# 06_POWER_4.net
KiCad netlist of a schematic drawn in Altium Designer
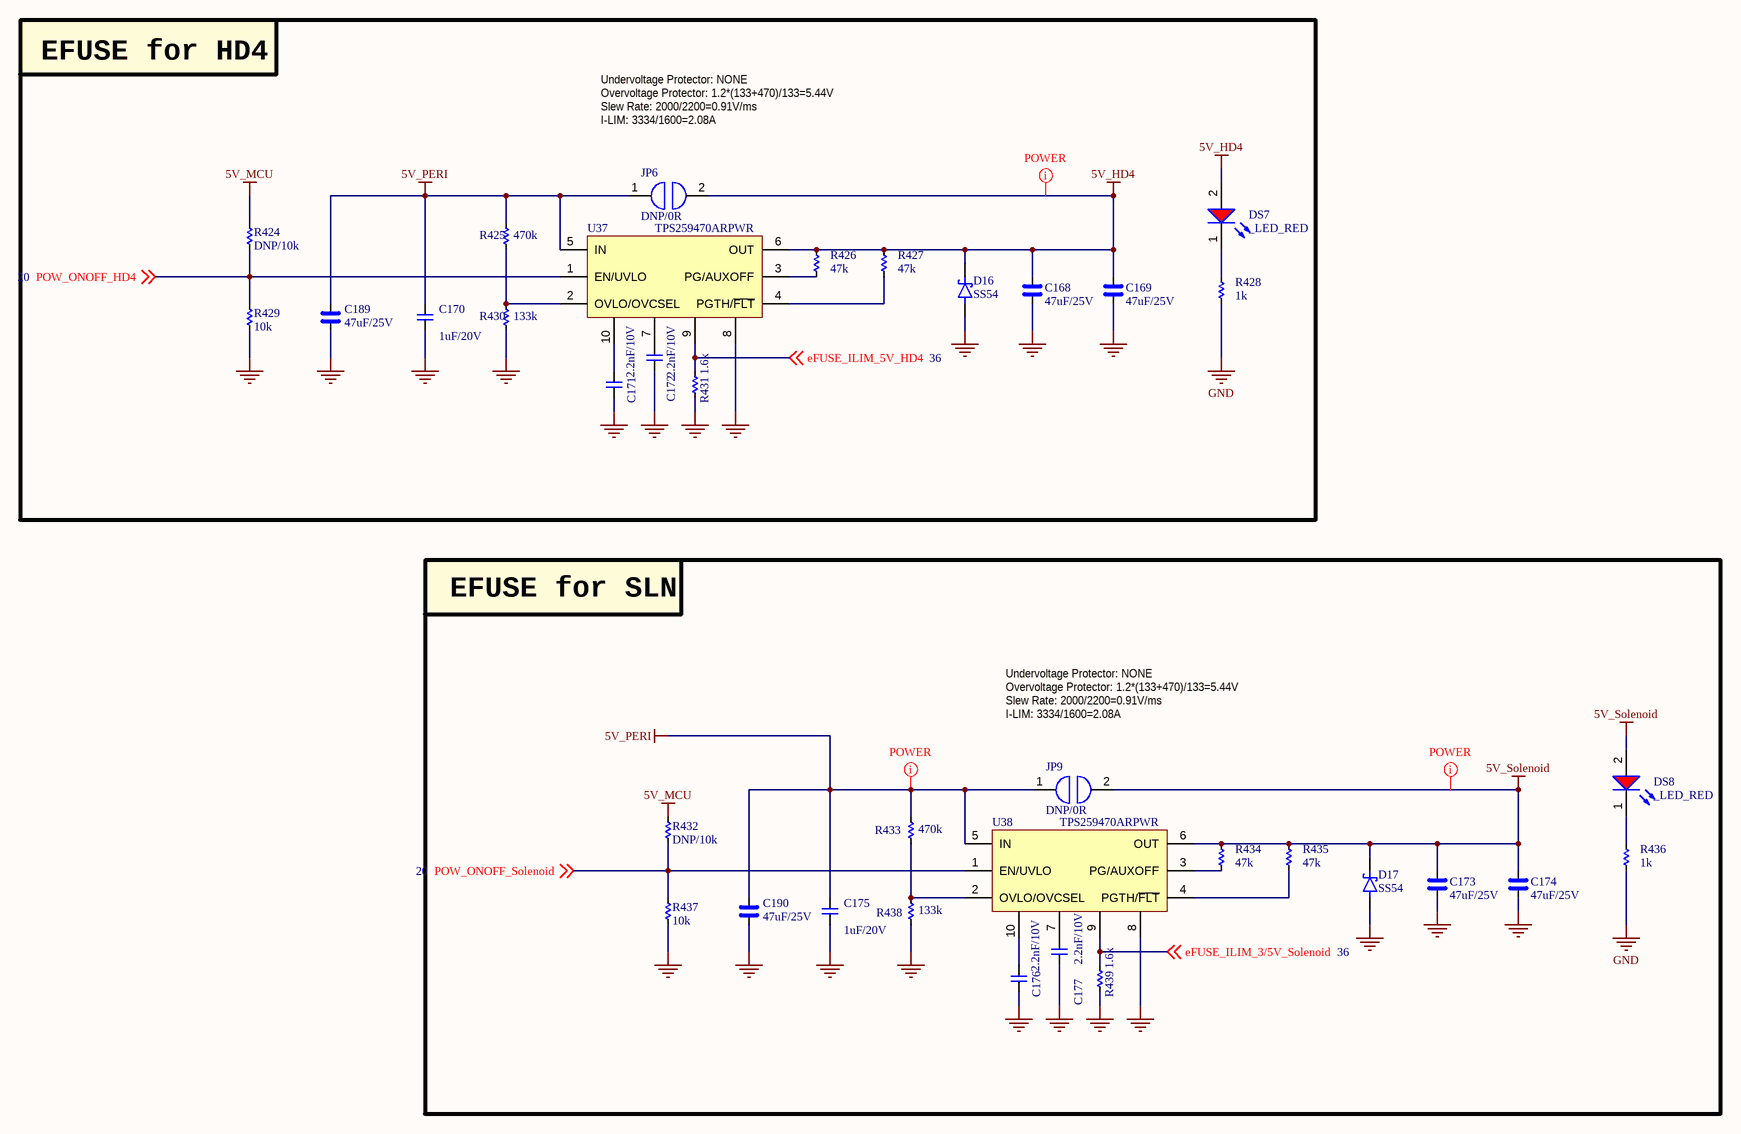
[diagram p0: 06_POWER_4.SchDoc]

(export (version "E")
  (design (tool "Eeschema 10.0.6"))
  (components
    (comp (ref "C168")
      (value "47uF/25V")
      (footprint "CAP_C_3225X80")
      (description "CAP High Value")
      (libsource (lib "LABLIB") (part "_CAP_C_High_2"))
    )
    (comp (ref "C169")
      (value "47uF/25V")
      (footprint "CAP_C_3225X80")
      (description "CAP High Value")
      (libsource (lib "LABLIB") (part "_CAP_C_High_2"))
    )
    (comp (ref "C170")
      (value "1uF/20V")
      (footprint "CAP_C_1005X60")
      (description "CAP")
      (libsource (lib "LABLIB") (part "_CAP_C_2"))
    )
    (comp (ref "C171")
      (value "2.2nF/10V")
      (footprint "CAP_C_1005X60")
      (description "CAP")
      (libsource (lib "LABLIB") (part "_CAP_C_2"))
    )
    (comp (ref "C172")
      (value "2.2nF/10V")
      (footprint "CAP_C_1005X60")
      (description "CAP")
      (libsource (lib "LABLIB") (part "_CAP_C_2"))
    )
    (comp (ref "C173")
      (value "47uF/25V")
      (footprint "CAP_C_3225X80")
      (description "CAP High Value")
      (libsource (lib "LABLIB") (part "_CAP_C_High_2"))
    )
    (comp (ref "C174")
      (value "47uF/25V")
      (footprint "CAP_C_3225X80")
      (description "CAP High Value")
      (libsource (lib "LABLIB") (part "_CAP_C_High_2"))
    )
    (comp (ref "C175")
      (value "1uF/20V")
      (footprint "CAP_C_1005X60")
      (description "CAP")
      (libsource (lib "LABLIB") (part "_CAP_C_2"))
    )
    (comp (ref "C176")
      (value "2.2nF/10V")
      (footprint "CAP_C_1005X60")
      (description "CAP")
      (libsource (lib "LABLIB") (part "_CAP_C_2"))
    )
    (comp (ref "C177")
      (value "2.2nF/10V")
      (footprint "CAP_C_1005X60")
      (description "CAP")
      (libsource (lib "LABLIB") (part "_CAP_C_2"))
    )
    (comp (ref "C189")
      (value "47uF/25V")
      (footprint "CAP_C_3225X80")
      (description "CAP High Value")
      (libsource (lib "LABLIB") (part "_CAP_C_High_2"))
    )
    (comp (ref "C190")
      (value "47uF/25V")
      (footprint "CAP_C_3225X80")
      (description "CAP High Value")
      (libsource (lib "LABLIB") (part "_CAP_C_High_2"))
    )
    (comp (ref "D16")
      (value "SS54")
      (footprint "DO-214AC_SMA")
      (description "DIODE SCHOTTKY")
      (libsource (lib "LABLIB") (part "DIODE SCHOTTKY"))
    )
    (comp (ref "D17")
      (value "SS54")
      (footprint "DO-214AC_SMA")
      (description "DIODE SCHOTTKY")
      (libsource (lib "LABLIB") (part "DIODE SCHOTTKY"))
    )
    (comp (ref "DS7") (value "_LED_RED") (footprint "LED_0603") (libsource (lib "LABLIB") (part "_LED_RED")))
    (comp (ref "DS8") (value "_LED_RED") (footprint "LED_0603") (libsource (lib "LABLIB") (part "_LED_RED")))
    (comp (ref "JP6") (value "DNP/0R") (footprint "JUMPER_1608") (libsource (lib "EXP_V1") (part "JUMPER")))
    (comp (ref "JP9") (value "DNP/0R") (footprint "JUMPER_1608") (libsource (lib "EXP_V1") (part "JUMPER")))
    (comp (ref "R424")
      (value "DNP/10k")
      (footprint "RES_C_1005X40")
      (description "RES")
      (libsource (lib "LABLIB") (part "_RES_B_2"))
    )
    (comp (ref "R425")
      (value "470k")
      (footprint "RES_C_1005X40")
      (description "RES")
      (libsource (lib "LABLIB") (part "_RES_B_2"))
    )
    (comp (ref "R426")
      (value "47k")
      (footprint "RES_C_1005X40")
      (description "RES")
      (libsource (lib "LABLIB") (part "_RES_B_2"))
    )
    (comp (ref "R427")
      (value "47k")
      (footprint "RES_C_1005X40")
      (description "RES")
      (libsource (lib "LABLIB") (part "_RES_B_2"))
    )
    (comp (ref "R428")
      (value "1k")
      (footprint "RES_C_1005X40")
      (description "RES")
      (libsource (lib "LABLIB") (part "_RES_B_2"))
    )
    (comp (ref "R429")
      (value "10k")
      (footprint "RES_C_1005X40")
      (description "RES")
      (libsource (lib "LABLIB") (part "_RES_B_2"))
    )
    (comp (ref "R430")
      (value "133k")
      (footprint "RES_C_1005X40")
      (description "RES")
      (libsource (lib "LABLIB") (part "_RES_B_2"))
    )
    (comp (ref "R431")
      (value "1.6k")
      (footprint "RES_C_1005X40")
      (description "RES")
      (libsource (lib "LABLIB") (part "_RES_B_2"))
    )
    (comp (ref "R432")
      (value "DNP/10k")
      (footprint "RES_C_1005X40")
      (description "RES")
      (libsource (lib "LABLIB") (part "_RES_B_2"))
    )
    (comp (ref "R433")
      (value "470k")
      (footprint "RES_C_1005X40")
      (description "RES")
      (libsource (lib "LABLIB") (part "_RES_B_2"))
    )
    (comp (ref "R434")
      (value "47k")
      (footprint "RES_C_1005X40")
      (description "RES")
      (libsource (lib "LABLIB") (part "_RES_B_2"))
    )
    (comp (ref "R435")
      (value "47k")
      (footprint "RES_C_1005X40")
      (description "RES")
      (libsource (lib "LABLIB") (part "_RES_B_2"))
    )
    (comp (ref "R436")
      (value "1k")
      (footprint "RES_C_1005X40")
      (description "RES")
      (libsource (lib "LABLIB") (part "_RES_B_2"))
    )
    (comp (ref "R437")
      (value "10k")
      (footprint "RES_C_1005X40")
      (description "RES")
      (libsource (lib "LABLIB") (part "_RES_B_2"))
    )
    (comp (ref "R438")
      (value "133k")
      (footprint "RES_C_1005X40")
      (description "RES")
      (libsource (lib "LABLIB") (part "_RES_B_2"))
    )
    (comp (ref "R439")
      (value "1.6k")
      (footprint "RES_C_1005X40")
      (description "RES")
      (libsource (lib "LABLIB") (part "_RES_B_2"))
    )
    (comp (ref "U37")
      (value "TPS259470ARPWR")
      (footprint "VQFN-HR-10")
      (libsource (lib "EXP_HW_V3") (part "TPS259470ARPWR"))
    )
    (comp (ref "U38")
      (value "TPS259470ARPWR")
      (footprint "VQFN-HR-10")
      (libsource (lib "EXP_HW_V3") (part "TPS259470ARPWR"))
    )
  )
  (nets
    (net (code "1") (name "5V_HD4") (class "Default")
      (node (ref "C168") (pin "2") (pinfunction "2_2") (pintype "passive"))
      (node (ref "C169") (pin "2") (pinfunction "2_2") (pintype "passive"))
      (node (ref "D16") (pin "1") (pinfunction "K_1") (pintype "passive"))
      (node (ref "DS7") (pin "2") (pinfunction "A_2") (pintype "passive"))
      (node (ref "JP6") (pin "2") (pinfunction "2_2") (pintype "passive"))
      (node (ref "R426") (pin "2") (pinfunction "2_2") (pintype "passive"))
      (node (ref "R427") (pin "2") (pinfunction "2_2") (pintype "passive"))
      (node (ref "U37") (pin "6") (pinfunction "OUT_6") (pintype "passive"))
    )
    (net (code "2") (name "5V_MCU") (class "Default")
      (node (ref "R424") (pin "1") (pinfunction "1_1") (pintype "passive"))
      (node (ref "R432") (pin "1") (pinfunction "1_1") (pintype "passive"))
    )
    (net (code "3") (name "5V_PERI") (class "Default")
      (node (ref "C170") (pin "2") (pinfunction "2_2") (pintype "passive"))
      (node (ref "C175") (pin "2") (pinfunction "2_2") (pintype "passive"))
      (node (ref "C189") (pin "2") (pinfunction "2_2") (pintype "passive"))
      (node (ref "C190") (pin "2") (pinfunction "2_2") (pintype "passive"))
      (node (ref "JP6") (pin "1") (pinfunction "1_1") (pintype "passive"))
      (node (ref "JP9") (pin "1") (pinfunction "1_1") (pintype "passive"))
      (node (ref "R425") (pin "2") (pinfunction "2_2") (pintype "passive"))
      (node (ref "R433") (pin "2") (pinfunction "2_2") (pintype "passive"))
      (node (ref "U37") (pin "5") (pinfunction "IN_5") (pintype "passive"))
      (node (ref "U38") (pin "5") (pinfunction "IN_5") (pintype "passive"))
    )
    (net (code "4") (name "5V_Solenoid") (class "Default")
      (node (ref "C173") (pin "2") (pinfunction "2_2") (pintype "passive"))
      (node (ref "C174") (pin "2") (pinfunction "2_2") (pintype "passive"))
      (node (ref "D17") (pin "1") (pinfunction "K_1") (pintype "passive"))
      (node (ref "DS8") (pin "2") (pinfunction "A_2") (pintype "passive"))
      (node (ref "JP9") (pin "2") (pinfunction "2_2") (pintype "passive"))
      (node (ref "R434") (pin "2") (pinfunction "2_2") (pintype "passive"))
      (node (ref "R435") (pin "2") (pinfunction "2_2") (pintype "passive"))
      (node (ref "U38") (pin "6") (pinfunction "OUT_6") (pintype "passive"))
    )
    (net (code "5") (name "GND") (class "Default")
      (node (ref "C168") (pin "1") (pinfunction "1_1") (pintype "passive"))
      (node (ref "C169") (pin "1") (pinfunction "1_1") (pintype "passive"))
      (node (ref "C170") (pin "1") (pinfunction "1_1") (pintype "passive"))
      (node (ref "C171") (pin "1") (pinfunction "1_1") (pintype "passive"))
      (node (ref "C172") (pin "1") (pinfunction "1_1") (pintype "passive"))
      (node (ref "C173") (pin "1") (pinfunction "1_1") (pintype "passive"))
      (node (ref "C174") (pin "1") (pinfunction "1_1") (pintype "passive"))
      (node (ref "C175") (pin "1") (pinfunction "1_1") (pintype "passive"))
      (node (ref "C176") (pin "1") (pinfunction "1_1") (pintype "passive"))
      (node (ref "C177") (pin "1") (pinfunction "1_1") (pintype "passive"))
      (node (ref "C189") (pin "1") (pinfunction "1_1") (pintype "passive"))
      (node (ref "C190") (pin "1") (pinfunction "1_1") (pintype "passive"))
      (node (ref "D16") (pin "2") (pinfunction "A_2") (pintype "passive"))
      (node (ref "D17") (pin "2") (pinfunction "A_2") (pintype "passive"))
      (node (ref "R428") (pin "1") (pinfunction "1_1") (pintype "passive"))
      (node (ref "R429") (pin "2") (pinfunction "2_2") (pintype "passive"))
      (node (ref "R430") (pin "1") (pinfunction "1_1") (pintype "passive"))
      (node (ref "R431") (pin "1") (pinfunction "1_1") (pintype "passive"))
      (node (ref "R436") (pin "1") (pinfunction "1_1") (pintype "passive"))
      (node (ref "R437") (pin "2") (pinfunction "2_2") (pintype "passive"))
      (node (ref "R438") (pin "1") (pinfunction "1_1") (pintype "passive"))
      (node (ref "R439") (pin "1") (pinfunction "1_1") (pintype "passive"))
      (node (ref "U37") (pin "8") (pinfunction "8_8") (pintype "passive"))
      (node (ref "U38") (pin "8") (pinfunction "8_8") (pintype "passive"))
    )
    (net (code "6") (name "Net-(C171-Pad2)") (class "Default")
      (node (ref "C171") (pin "2") (pinfunction "2_2") (pintype "passive"))
      (node (ref "U37") (pin "10") (pinfunction "10_10") (pintype "passive"))
    )
    (net (code "7") (name "Net-(C172-Pad2)") (class "Default")
      (node (ref "C172") (pin "2") (pinfunction "2_2") (pintype "passive"))
      (node (ref "U37") (pin "7") (pinfunction "7_7") (pintype "passive"))
    )
    (net (code "8") (name "Net-(C176-Pad2)") (class "Default")
      (node (ref "C176") (pin "2") (pinfunction "2_2") (pintype "passive"))
      (node (ref "U38") (pin "10") (pinfunction "10_10") (pintype "passive"))
    )
    (net (code "9") (name "Net-(C177-Pad2)") (class "Default")
      (node (ref "C177") (pin "2") (pinfunction "2_2") (pintype "passive"))
      (node (ref "U38") (pin "7") (pinfunction "7_7") (pintype "passive"))
    )
    (net (code "10") (name "Net-(DS7-K)") (class "Default")
      (node (ref "DS7") (pin "1") (pinfunction "K_1") (pintype "passive"))
      (node (ref "R428") (pin "2") (pinfunction "2_2") (pintype "passive"))
    )
    (net (code "11") (name "Net-(DS8-K)") (class "Default")
      (node (ref "DS8") (pin "1") (pinfunction "K_1") (pintype "passive"))
      (node (ref "R436") (pin "2") (pinfunction "2_2") (pintype "passive"))
    )
    (net (code "12") (name "Net-(U37-OVLO{slash}OVCSEL)") (class "Default")
      (node (ref "R425") (pin "1") (pinfunction "1_1") (pintype "passive"))
      (node (ref "R430") (pin "2") (pinfunction "2_2") (pintype "passive"))
      (node (ref "U37") (pin "2") (pinfunction "OVLO/OVCSEL_2") (pintype "passive"))
    )
    (net (code "13") (name "Net-(U37-PGTH{slash}~{FLT})") (class "Default")
      (node (ref "R427") (pin "1") (pinfunction "1_1") (pintype "passive"))
      (node (ref "U37") (pin "4") (pinfunction "PGTH/~{FLT}_4") (pintype "passive"))
    )
    (net (code "14") (name "Net-(U37-PG{slash}AUXOFF)") (class "Default")
      (node (ref "R426") (pin "1") (pinfunction "1_1") (pintype "passive"))
      (node (ref "U37") (pin "3") (pinfunction "PG/AUXOFF_3") (pintype "passive"))
    )
    (net (code "15") (name "Net-(U38-OVLO{slash}OVCSEL)") (class "Default")
      (node (ref "R433") (pin "1") (pinfunction "1_1") (pintype "passive"))
      (node (ref "R438") (pin "2") (pinfunction "2_2") (pintype "passive"))
      (node (ref "U38") (pin "2") (pinfunction "OVLO/OVCSEL_2") (pintype "passive"))
    )
    (net (code "16") (name "Net-(U38-PGTH{slash}~{FLT})") (class "Default")
      (node (ref "R435") (pin "1") (pinfunction "1_1") (pintype "passive"))
      (node (ref "U38") (pin "4") (pinfunction "PGTH/~{FLT}_4") (pintype "passive"))
    )
    (net (code "17") (name "Net-(U38-PG{slash}AUXOFF)") (class "Default")
      (node (ref "R434") (pin "1") (pinfunction "1_1") (pintype "passive"))
      (node (ref "U38") (pin "3") (pinfunction "PG/AUXOFF_3") (pintype "passive"))
    )
    (net (code "18") (name "POW_ONOFF_HD4") (class "Default")
      (node (ref "R424") (pin "2") (pinfunction "2_2") (pintype "passive"))
      (node (ref "R429") (pin "1") (pinfunction "1_1") (pintype "passive"))
      (node (ref "U37") (pin "1") (pinfunction "EN/UVLO_1") (pintype "passive"))
    )
    (net (code "19") (name "POW_ONOFF_Solenoid") (class "Default")
      (node (ref "R432") (pin "2") (pinfunction "2_2") (pintype "passive"))
      (node (ref "R437") (pin "1") (pinfunction "1_1") (pintype "passive"))
      (node (ref "U38") (pin "1") (pinfunction "EN/UVLO_1") (pintype "passive"))
    )
    (net (code "20") (name "eFUSE_ILIM_3{slash}5V_Solenoid") (class "Default")
      (node (ref "R439") (pin "2") (pinfunction "2_2") (pintype "passive"))
      (node (ref "U38") (pin "9") (pinfunction "9_9") (pintype "passive"))
    )
    (net (code "21") (name "eFUSE_ILIM_5V_HD4") (class "Default")
      (node (ref "R431") (pin "2") (pinfunction "2_2") (pintype "passive"))
      (node (ref "U37") (pin "9") (pinfunction "9_9") (pintype "passive"))
    )
  )
)
